# V1_9.net
KiCad netlist of a schematic drawn in Altium Designer
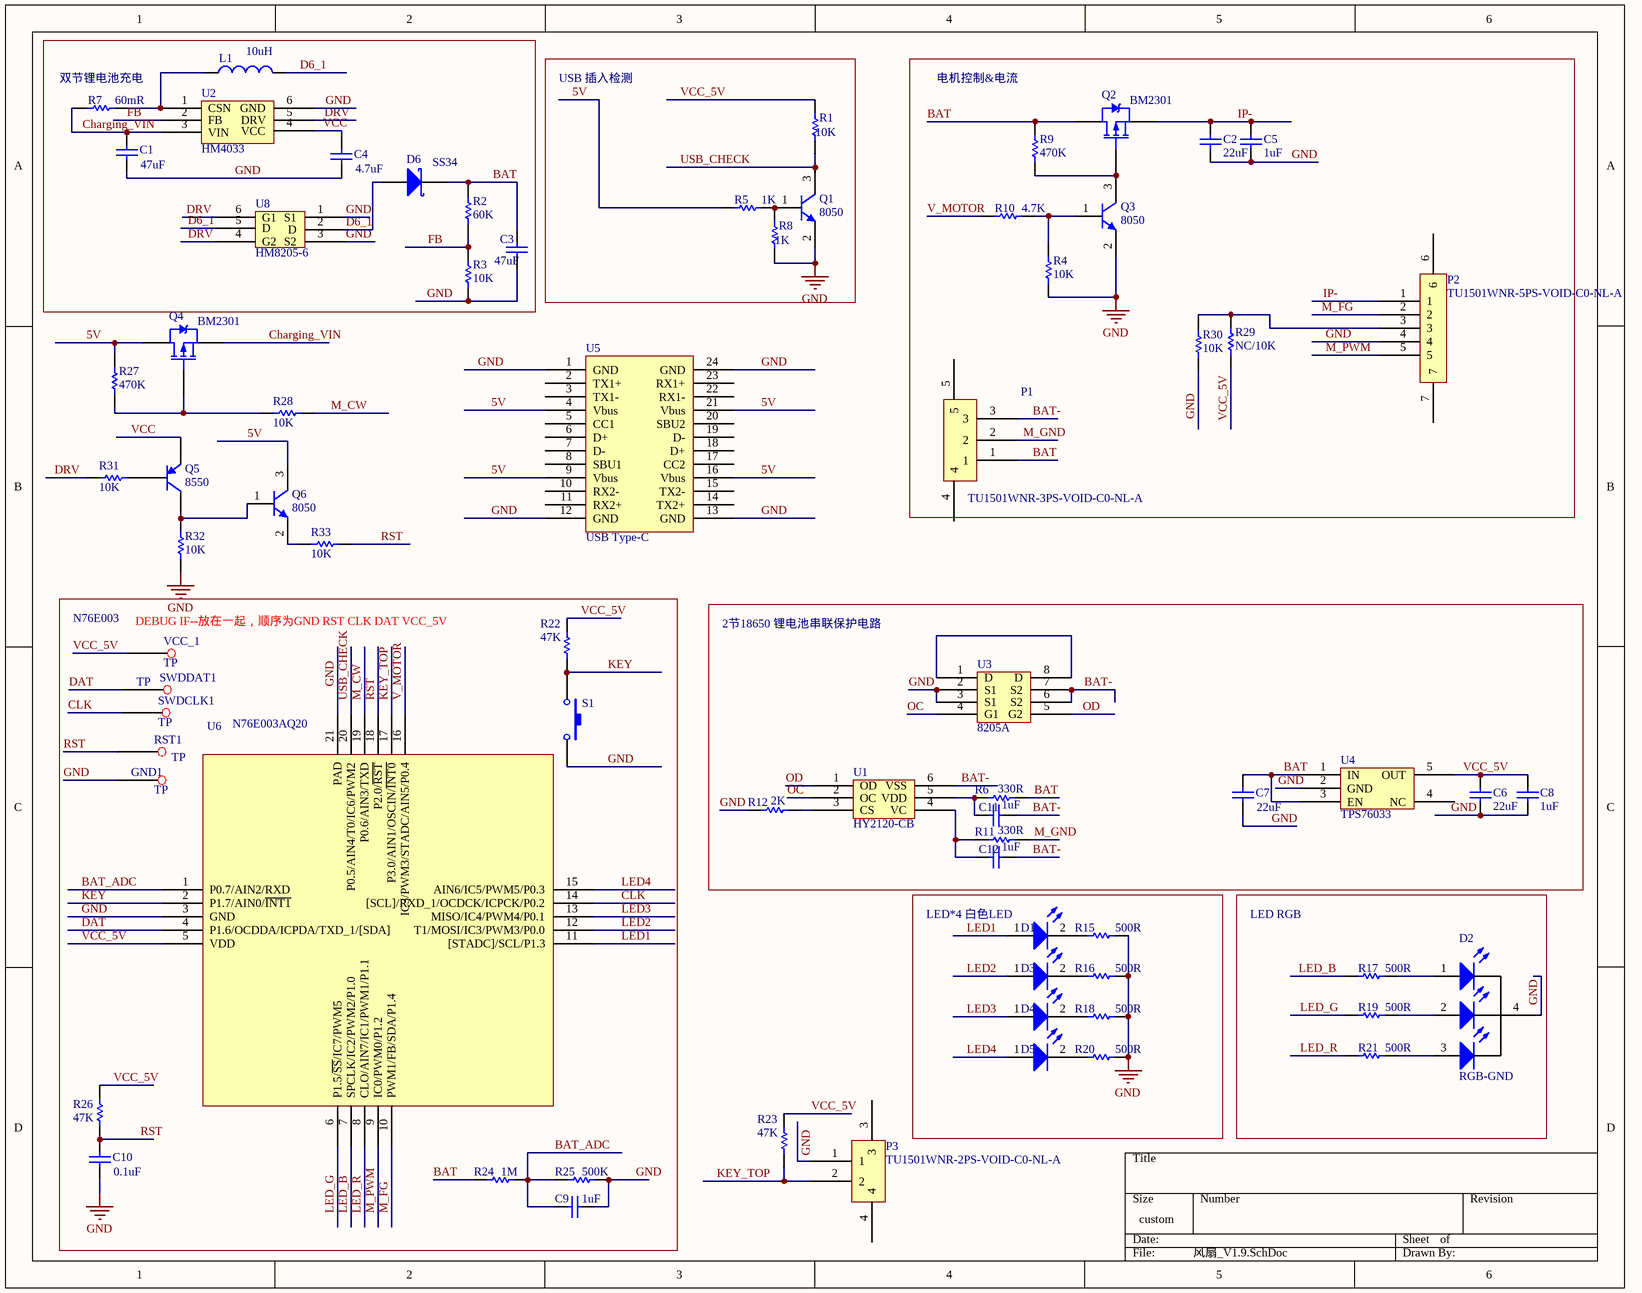
[diagram p0: 风扇_V1.9.SchDoc]

(export (version "E")
  (design (tool "Eeschema 10.0.6"))
  (components
    (comp (ref "C1")
      (value "47uF")
      (footprint "C-0603")
      (description "Capacitor")
      (fields (field (name "PUBLISHER") "Altium Limited"))
      (libsource (lib "Miscellaneous Devices") (part "Cap"))
    )
    (comp (ref "C2")
      (value "22uF")
      (footprint "C-0603")
      (description "Capacitor")
      (fields (field (name "PUBLISHER") "Altium Limited"))
      (libsource (lib "Miscellaneous Devices") (part "Cap"))
    )
    (comp (ref "C3")
      (value "47uF")
      (footprint "C-0603")
      (description "Capacitor")
      (fields (field (name "PUBLISHER") "Altium Limited"))
      (libsource (lib "Miscellaneous Devices") (part "Cap"))
    )
    (comp (ref "C4")
      (value "4.7uF")
      (footprint "C-0402")
      (description "Capacitor")
      (fields (field (name "PUBLISHER") "Altium Limited"))
      (libsource (lib "Miscellaneous Devices") (part "Cap"))
    )
    (comp (ref "C5")
      (value "1uF")
      (footprint "C-0402")
      (description "Capacitor")
      (fields (field (name "PUBLISHER") "Altium Limited"))
      (libsource (lib "Miscellaneous Devices") (part "Cap"))
    )
    (comp (ref "C6")
      (value "22uF")
      (footprint "C-0603")
      (description "Capacitor")
      (fields (field (name "PUBLISHER") "Altium Limited"))
      (libsource (lib "Miscellaneous Devices") (part "Cap"))
    )
    (comp (ref "C7")
      (value "22uF")
      (footprint "C-0603")
      (description "Capacitor")
      (fields (field (name "PUBLISHER") "Altium Limited"))
      (libsource (lib "Miscellaneous Devices") (part "Cap"))
    )
    (comp (ref "C8")
      (value "1uF")
      (footprint "C-0402")
      (description "Capacitor")
      (fields (field (name "PUBLISHER") "Altium Limited"))
      (libsource (lib "Miscellaneous Devices") (part "Cap"))
    )
    (comp (ref "C9")
      (value "1uF")
      (footprint "C-0402")
      (description "Capacitor")
      (fields (field (name "PUBLISHER") "Altium Limited"))
      (libsource (lib "Miscellaneous Devices") (part "Cap"))
    )
    (comp (ref "C10")
      (value "0.1uF")
      (footprint "C-0402")
      (description "Capacitor")
      (fields (field (name "PUBLISHER") "Altium Limited"))
      (libsource (lib "Miscellaneous Devices") (part "Cap"))
    )
    (comp (ref "C11")
      (value "1uF")
      (footprint "C-0402")
      (description "Capacitor")
      (fields (field (name "PUBLISHER") "Altium Limited"))
      (libsource (lib "Miscellaneous Devices") (part "Cap"))
    )
    (comp (ref "C12")
      (value "1uF")
      (footprint "C-0402")
      (description "Capacitor")
      (fields (field (name "PUBLISHER") "Altium Limited"))
      (libsource (lib "Miscellaneous Devices") (part "Cap"))
    )
    (comp (ref "D1")
      (value "LED0")
      (footprint "LED-0603")
      (description "Typical INFRARED GaAs LED")
      (fields (field (name "PUBLISHER") "Altium Limited"))
      (libsource (lib "Miscellaneous Devices") (part "LED0"))
    )
    (comp (ref "D2")
      (value "RGB-GND")
      (footprint "0603*2-LED")
      (libsource (lib "Others_IC_SCH_LIB") (part "RGB-GND"))
    )
    (comp (ref "D3")
      (value "LED0")
      (footprint "LED-0603")
      (description "Typical INFRARED GaAs LED")
      (fields (field (name "PUBLISHER") "Altium Limited"))
      (libsource (lib "Miscellaneous Devices") (part "LED0"))
    )
    (comp (ref "D4")
      (value "LED0")
      (footprint "LED-0603")
      (description "Typical INFRARED GaAs LED")
      (fields (field (name "PUBLISHER") "Altium Limited"))
      (libsource (lib "Miscellaneous Devices") (part "LED0"))
    )
    (comp (ref "D5")
      (value "LED0")
      (footprint "LED-0603")
      (description "Typical INFRARED GaAs LED")
      (fields (field (name "PUBLISHER") "Altium Limited"))
      (libsource (lib "Miscellaneous Devices") (part "LED0"))
    )
    (comp (ref "D6")
      (value "SS34")
      (footprint "HM4033 V1.0:DSMD")
      (description "Schottky Rectifier")
      (fields (field (name "PUBLISHER") "Altium Limited"))
      (libsource (lib "Miscellaneous Devices") (part "Diode 10TQ035"))
    )
    (comp (ref "GND1") (value "TP") (footprint "TP-1.5") (libsource (lib "Others_IC_SCH_LIB") (part "TP")))
    (comp (ref "L1")
      (value "10uH")
      (footprint "L-SMD")
      (description "Inductor")
      (fields (field (name "PUBLISHER") "Altium Limited"))
      (libsource (lib "Miscellaneous Devices") (part "Inductor"))
    )
    (comp (ref "P1")
      (value "TU1501WNR-3PS-VOID-C0-NL-A")
      (footprint "TU1501WNR-3PS-VOID-*-NL-A")
      (libsource (lib "Others_IC_SCH_LIB") (part "TU1501WNR-3PS-VOID-C0-NL-A"))
    )
    (comp (ref "P2")
      (value "TU1501WNR-5PS-VOID-C0-NL-A")
      (footprint "TU1501WNR-5PS-VOID-*-NL-A")
      (libsource (lib "Others_IC_SCH_LIB") (part "TU1501WNR-5PS-VOID-C0-NL-A"))
    )
    (comp (ref "P3")
      (value "TU1501WNR-2PS-VOID-C0-NL-A")
      (footprint "TU1501WNR-2PS-VOID-*-NL-A")
      (libsource (lib "Others_IC_SCH_LIB") (part "TU1501WNR-2PS-VOID-C0-NL-A"))
    )
    (comp (ref "Q1")
      (value "8050")
      (footprint "SOT-23")
      (description "NPN Bipolar Transistor")
      (fields (field (name "PUBLISHER") "Altium Limited"))
      (libsource (lib "Miscellaneous Devices") (part "NPN"))
    )
    (comp (ref "Q2")
      (value "BM2301")
      (footprint "SOT-23")
      (description "P-Channel Power MOSFET")
      (fields (field (name "PUBLISHER") "Altium Limited"))
      (libsource (lib "Miscellaneous Devices") (part "PMOS-2"))
    )
    (comp (ref "Q3")
      (value "8050")
      (footprint "SOT-23")
      (description "NPN Bipolar Transistor")
      (fields (field (name "PUBLISHER") "Altium Limited"))
      (libsource (lib "Miscellaneous Devices") (part "NPN"))
    )
    (comp (ref "Q4")
      (value "BM2301")
      (footprint "SOT-23")
      (description "P-Channel Power MOSFET")
      (fields (field (name "PUBLISHER") "Altium Limited"))
      (libsource (lib "Miscellaneous Devices") (part "PMOS-2"))
    )
    (comp (ref "Q5")
      (value "8550")
      (footprint "SOT95P240-3N")
      (description "PNP Bipolar Transistor")
      (fields (field (name "PUBLISHER") "Altium Limited"))
      (libsource (lib "Miscellaneous Devices") (part "PNP"))
    )
    (comp (ref "Q6")
      (value "8050")
      (footprint "SOT-23")
      (description "NPN Bipolar Transistor")
      (fields (field (name "PUBLISHER") "Altium Limited"))
      (libsource (lib "Miscellaneous Devices") (part "NPN"))
    )
    (comp (ref "R1")
      (value "10K")
      (footprint "R-0402")
      (description "Resistor")
      (fields (field (name "PUBLISHER") "Altium Limited"))
      (libsource (lib "Miscellaneous Devices") (part "Res1"))
    )
    (comp (ref "R2")
      (value "60K")
      (footprint "R-0402")
      (description "Resistor")
      (fields (field (name "PUBLISHER") "Altium Limited"))
      (libsource (lib "Miscellaneous Devices") (part "Res1"))
    )
    (comp (ref "R3")
      (value "10K")
      (footprint "R-0402")
      (description "Resistor")
      (fields (field (name "PUBLISHER") "Altium Limited"))
      (libsource (lib "Miscellaneous Devices") (part "Res1"))
    )
    (comp (ref "R4")
      (value "10K")
      (footprint "R-0402")
      (description "Resistor")
      (fields (field (name "PUBLISHER") "Altium Limited"))
      (libsource (lib "Miscellaneous Devices") (part "Res1"))
    )
    (comp (ref "R5")
      (value "1K")
      (footprint "R-0402")
      (description "Resistor")
      (fields (field (name "PUBLISHER") "Altium Limited"))
      (libsource (lib "Miscellaneous Devices") (part "Res1"))
    )
    (comp (ref "R6")
      (value "330R")
      (footprint "R-0402")
      (description "Resistor")
      (fields (field (name "PUBLISHER") "Altium Limited"))
      (libsource (lib "Miscellaneous Devices") (part "Res1"))
    )
    (comp (ref "R7")
      (value "60mR")
      (footprint "R-0402")
      (description "Resistor")
      (fields (field (name "PUBLISHER") "Altium Limited"))
      (libsource (lib "Miscellaneous Devices") (part "Res1"))
    )
    (comp (ref "R8")
      (value "1K")
      (footprint "R-0402")
      (description "Resistor")
      (fields (field (name "PUBLISHER") "Altium Limited"))
      (libsource (lib "Miscellaneous Devices") (part "Res1"))
    )
    (comp (ref "R9")
      (value "470K")
      (footprint "R-0402")
      (description "Resistor")
      (fields (field (name "PUBLISHER") "Altium Limited"))
      (libsource (lib "Miscellaneous Devices") (part "Res1"))
    )
    (comp (ref "R10")
      (value "4.7K")
      (footprint "R-0402")
      (description "Resistor")
      (fields (field (name "PUBLISHER") "Altium Limited"))
      (libsource (lib "Miscellaneous Devices") (part "Res1"))
    )
    (comp (ref "R11")
      (value "330R")
      (footprint "R-0402")
      (description "Resistor")
      (fields (field (name "PUBLISHER") "Altium Limited"))
      (libsource (lib "Miscellaneous Devices") (part "Res1"))
    )
    (comp (ref "R12")
      (value "2K")
      (footprint "R-0402")
      (description "Resistor")
      (fields (field (name "PUBLISHER") "Altium Limited"))
      (libsource (lib "Miscellaneous Devices") (part "Res1"))
    )
    (comp (ref "R15")
      (value "500R")
      (footprint "R-0402")
      (description "Resistor")
      (fields (field (name "PUBLISHER") "Altium Limited"))
      (libsource (lib "Miscellaneous Devices") (part "Res1"))
    )
    (comp (ref "R16")
      (value "500R")
      (footprint "R-0402")
      (description "Resistor")
      (fields (field (name "PUBLISHER") "Altium Limited"))
      (libsource (lib "Miscellaneous Devices") (part "Res1"))
    )
    (comp (ref "R17")
      (value "500R")
      (footprint "R-0402")
      (description "Resistor")
      (fields (field (name "PUBLISHER") "Altium Limited"))
      (libsource (lib "Miscellaneous Devices") (part "Res1"))
    )
    (comp (ref "R18")
      (value "500R")
      (footprint "R-0402")
      (description "Resistor")
      (fields (field (name "PUBLISHER") "Altium Limited"))
      (libsource (lib "Miscellaneous Devices") (part "Res1"))
    )
    (comp (ref "R19")
      (value "500R")
      (footprint "R-0402")
      (description "Resistor")
      (fields (field (name "PUBLISHER") "Altium Limited"))
      (libsource (lib "Miscellaneous Devices") (part "Res1"))
    )
    (comp (ref "R20")
      (value "500R")
      (footprint "R-0402")
      (description "Resistor")
      (fields (field (name "PUBLISHER") "Altium Limited"))
      (libsource (lib "Miscellaneous Devices") (part "Res1"))
    )
    (comp (ref "R21")
      (value "500R")
      (footprint "R-0402")
      (description "Resistor")
      (fields (field (name "PUBLISHER") "Altium Limited"))
      (libsource (lib "Miscellaneous Devices") (part "Res1"))
    )
    (comp (ref "R22")
      (value "47K")
      (footprint "R-0402")
      (description "Resistor")
      (fields (field (name "PUBLISHER") "Altium Limited"))
      (libsource (lib "Miscellaneous Devices") (part "Res1"))
    )
    (comp (ref "R23")
      (value "47K")
      (footprint "R-0402")
      (description "Resistor")
      (fields (field (name "PUBLISHER") "Altium Limited"))
      (libsource (lib "Miscellaneous Devices") (part "Res1"))
    )
    (comp (ref "R24")
      (value "1M")
      (footprint "R-0402")
      (description "Resistor")
      (fields (field (name "PUBLISHER") "Altium Limited"))
      (libsource (lib "Miscellaneous Devices") (part "Res1"))
    )
    (comp (ref "R25")
      (value "500K")
      (footprint "R-0402")
      (description "Resistor")
      (fields (field (name "PUBLISHER") "Altium Limited"))
      (libsource (lib "Miscellaneous Devices") (part "Res1"))
    )
    (comp (ref "R26")
      (value "47K")
      (footprint "R-0402")
      (description "Resistor")
      (fields (field (name "PUBLISHER") "Altium Limited"))
      (libsource (lib "Miscellaneous Devices") (part "Res1"))
    )
    (comp (ref "R27")
      (value "470K")
      (footprint "R-0402")
      (description "Resistor")
      (fields (field (name "PUBLISHER") "Altium Limited"))
      (libsource (lib "Miscellaneous Devices") (part "Res1"))
    )
    (comp (ref "R28")
      (value "10K")
      (footprint "R-0402")
      (description "Resistor")
      (fields (field (name "PUBLISHER") "Altium Limited"))
      (libsource (lib "Miscellaneous Devices") (part "Res1"))
    )
    (comp (ref "R29")
      (value "NC/10K")
      (footprint "R-0402")
      (description "Resistor")
      (fields (field (name "PUBLISHER") "Altium Limited"))
      (libsource (lib "Miscellaneous Devices") (part "Res1"))
    )
    (comp (ref "R30")
      (value "10K")
      (footprint "R-0402")
      (description "Resistor")
      (fields (field (name "PUBLISHER") "Altium Limited"))
      (libsource (lib "Miscellaneous Devices") (part "Res1"))
    )
    (comp (ref "R31")
      (value "10K")
      (footprint "R-0402")
      (description "Resistor")
      (fields (field (name "PUBLISHER") "Altium Limited"))
      (libsource (lib "Miscellaneous Devices") (part "Res1"))
    )
    (comp (ref "R32")
      (value "10K")
      (footprint "R-0402")
      (description "Resistor")
      (fields (field (name "PUBLISHER") "Altium Limited"))
      (libsource (lib "Miscellaneous Devices") (part "Res1"))
    )
    (comp (ref "R33")
      (value "10K")
      (footprint "R-0402")
      (description "Resistor")
      (fields (field (name "PUBLISHER") "Altium Limited"))
      (libsource (lib "Miscellaneous Devices") (part "Res1"))
    )
    (comp (ref "RST1") (value "TP") (footprint "TP-1.5") (libsource (lib "Others_IC_SCH_LIB") (part "TP")))
    (comp (ref "S1")
      (value "SW-PB")
      (footprint "SWITCH-4P-SMT")
      (description "Switch")
      (fields (field (name "PUBLISHER") "Altium Limited"))
      (libsource (lib "Miscellaneous Devices") (part "SW-PB"))
    )
    (comp (ref "SWDCLK1") (value "TP") (footprint "TP-1.5") (libsource (lib "Others_IC_SCH_LIB") (part "TP")))
    (comp (ref "SWDDAT1") (value "TP") (footprint "TP-1.5") (libsource (lib "Others_IC_SCH_LIB") (part "TP")))
    (comp (ref "U1")
      (value "HY2120-CB")
      (footprint "SOT-23-6L")
      (libsource (lib "Others_IC_SCH_LIB") (part "HY2120"))
    )
    (comp (ref "U2")
      (value "HM4033")
      (footprint "SOT-23-6L")
      (libsource (lib "Others_IC_SCH_LIB") (part "HM4033"))
    )
    (comp (ref "U3")
      (value "8205A")
      (footprint "TSSOP8")
      (libsource (lib "Others_IC_SCH_LIB") (part "8205A"))
    )
    (comp (ref "U4")
      (value "TPS76033")
      (footprint "SOT-23-5")
      (libsource (lib "Others_IC_SCH_LIB") (part "TPS76033"))
    )
    (comp (ref "U5")
      (value "USB Type-C")
      (footprint "USB-type C")
      (libsource (lib "Others_IC_SCH_LIB") (part "USB Type-C"))
    )
    (comp (ref "U6")
      (value "N76E003AQ20")
      (footprint "QFN-20 0.4mm")
      (libsource (lib "Others_IC_SCH_LIB") (part "N76E003AQ20"))
    )
    (comp (ref "U8")
      (value "HM8205-6")
      (footprint "SOT-23-6L")
      (libsource (lib "Others_IC_SCH_LIB") (part "HM8205-6"))
    )
    (comp (ref "VCC_1") (value "TP") (footprint "TP-1.5") (libsource (lib "Others_IC_SCH_LIB") (part "TP")))
  )
  (nets
    (net (code "1") (name "/5V") (class "Default")
      (node (ref "Q4") (pin "2") (pinfunction "D_2") (pintype "passive"))
      (node (ref "Q6") (pin "3") (pinfunction "C_3") (pintype "passive"))
      (node (ref "R27") (pin "2") (pinfunction "2_2") (pintype "passive"))
      (node (ref "R5") (pin "1") (pinfunction "1_1") (pintype "passive"))
      (node (ref "U5") (pin "16") (pinfunction "Vbus_16") (pintype "passive"))
      (node (ref "U5") (pin "21") (pinfunction "Vbus_21") (pintype "passive"))
      (node (ref "U5") (pin "4") (pinfunction "Vbus_4") (pintype "passive"))
      (node (ref "U5") (pin "9") (pinfunction "Vbus_9") (pintype "passive"))
    )
    (net (code "2") (name "/BAT") (class "Default")
      (node (ref "C3") (pin "2") (pinfunction "2_2") (pintype "passive"))
      (node (ref "C7") (pin "2") (pinfunction "2_2") (pintype "passive"))
      (node (ref "D6") (pin "1") (pinfunction "K_1") (pintype "passive"))
      (node (ref "P1") (pin "1") (pinfunction "1_1") (pintype "passive"))
      (node (ref "Q2") (pin "2") (pinfunction "D_2") (pintype "passive"))
      (node (ref "R2") (pin "1") (pinfunction "1_1") (pintype "passive"))
      (node (ref "R24") (pin "1") (pinfunction "1_1") (pintype "passive"))
      (node (ref "R6") (pin "2") (pinfunction "2_2") (pintype "passive"))
      (node (ref "R9") (pin "2") (pinfunction "2_2") (pintype "passive"))
      (node (ref "U4") (pin "1") (pinfunction "IN_1") (pintype "passive"))
      (node (ref "U4") (pin "3") (pinfunction "EN_3") (pintype "passive"))
    )
    (net (code "3") (name "/BAT-") (class "Default")
      (node (ref "C11") (pin "1") (pinfunction "1_1") (pintype "passive"))
      (node (ref "C12") (pin "1") (pinfunction "1_1") (pintype "passive"))
      (node (ref "P1") (pin "3") (pinfunction "3_3") (pintype "passive"))
      (node (ref "U1") (pin "6") (pinfunction "VSS_6") (pintype "passive"))
      (node (ref "U3") (pin "6") (pinfunction "S2_6") (pintype "passive"))
      (node (ref "U3") (pin "7") (pinfunction "S2_7") (pintype "passive"))
    )
    (net (code "4") (name "/BAT_ADC") (class "Default")
      (node (ref "C9") (pin "2") (pinfunction "2_2") (pintype "passive"))
      (node (ref "R24") (pin "2") (pinfunction "2_2") (pintype "passive"))
      (node (ref "R25") (pin "1") (pinfunction "1_1") (pintype "passive"))
      (node (ref "U6") (pin "1") (pinfunction "P0.7/AIN2/RXD_1") (pintype "passive"))
    )
    (net (code "5") (name "/CLK") (class "Default")
      (node (ref "SWDCLK1") (pin "1") (pinfunction "1_1") (pintype "passive"))
      (node (ref "U6") (pin "14") (pinfunction "[SCL]/RXD_1/OCDCK/ICPCK/P0.2_14") (pintype "passive"))
    )
    (net (code "6") (name "/Charging_VIN") (class "Default")
      (node (ref "C1") (pin "1") (pinfunction "1_1") (pintype "passive"))
      (node (ref "Q4") (pin "3") (pinfunction "S_3") (pintype "passive"))
      (node (ref "R7") (pin "2") (pinfunction "2_2") (pintype "passive"))
      (node (ref "U2") (pin "3") (pinfunction "VIN_3") (pintype "passive"))
    )
    (net (code "7") (name "/D6_1") (class "Default")
      (node (ref "D6") (pin "3") (pinfunction "A_3") (pintype "passive"))
      (node (ref "L1") (pin "2") (pinfunction "2_2") (pintype "passive"))
      (node (ref "U8") (pin "2") (pinfunction "D_2") (pintype "passive"))
      (node (ref "U8") (pin "5") (pinfunction "D_5") (pintype "passive"))
    )
    (net (code "8") (name "/DAT") (class "Default")
      (node (ref "SWDDAT1") (pin "1") (pinfunction "1_1") (pintype "passive"))
      (node (ref "U6") (pin "4") (pinfunction "P1.6/OCDDA/ICPDA/TXD_1/[SDA]_4") (pintype "passive"))
    )
    (net (code "9") (name "/DRV") (class "Default")
      (node (ref "R31") (pin "1") (pinfunction "1_1") (pintype "passive"))
      (node (ref "U2") (pin "5") (pinfunction "DRV_5") (pintype "passive"))
      (node (ref "U8") (pin "4") (pinfunction "G2_4") (pintype "passive"))
      (node (ref "U8") (pin "6") (pinfunction "G1_6") (pintype "passive"))
    )
    (net (code "10") (name "/FB") (class "Default")
      (node (ref "R2") (pin "2") (pinfunction "2_2") (pintype "passive"))
      (node (ref "R3") (pin "1") (pinfunction "1_1") (pintype "passive"))
      (node (ref "U2") (pin "2") (pinfunction "FB_2") (pintype "passive"))
    )
    (net (code "11") (name "/IP-") (class "Default")
      (node (ref "C2") (pin "2") (pinfunction "2_2") (pintype "passive"))
      (node (ref "C5") (pin "2") (pinfunction "2_2") (pintype "passive"))
      (node (ref "P2") (pin "1") (pinfunction "1_1") (pintype "passive"))
      (node (ref "Q2") (pin "3") (pinfunction "S_3") (pintype "passive"))
    )
    (net (code "12") (name "/KEY") (class "Default")
      (node (ref "R22") (pin "1") (pinfunction "1_1") (pintype "passive"))
      (node (ref "S1") (pin "1") (pinfunction "1_1") (pintype "passive"))
      (node (ref "U6") (pin "2") (pinfunction "P1.7/AIN0/~{INT1}_2") (pintype "passive"))
    )
    (net (code "13") (name "/KEY_TOP") (class "Default")
      (node (ref "P3") (pin "2") (pinfunction "2_2") (pintype "passive"))
      (node (ref "R23") (pin "1") (pinfunction "1_1") (pintype "passive"))
      (node (ref "U6") (pin "17") (pinfunction "P3.0/AIN1/OSCIN/~{INT0}_17") (pintype "passive"))
    )
    (net (code "14") (name "/LED1") (class "Default")
      (node (ref "D1") (pin "1") (pinfunction "A_1") (pintype "passive"))
      (node (ref "U6") (pin "11") (pinfunction "[STADC]/SCL/P1.3_11") (pintype "passive"))
    )
    (net (code "15") (name "/LED2") (class "Default")
      (node (ref "D3") (pin "1") (pinfunction "A_1") (pintype "passive"))
      (node (ref "U6") (pin "12") (pinfunction "T1/MOSI/IC3/PWM3/P0.0_12") (pintype "passive"))
    )
    (net (code "16") (name "/LED3") (class "Default")
      (node (ref "D4") (pin "1") (pinfunction "A_1") (pintype "passive"))
      (node (ref "U6") (pin "13") (pinfunction "MISO/IC4/PWM4/P0.1_13") (pintype "passive"))
    )
    (net (code "17") (name "/LED4") (class "Default")
      (node (ref "D5") (pin "1") (pinfunction "A_1") (pintype "passive"))
      (node (ref "U6") (pin "15") (pinfunction "AIN6/IC5/PWM5/P0.3_15") (pintype "passive"))
    )
    (net (code "18") (name "/LED_B") (class "Default")
      (node (ref "R17") (pin "1") (pinfunction "1_1") (pintype "passive"))
      (node (ref "U6") (pin "7") (pinfunction "SPCLK/IC2/PWM2/P1.0_7") (pintype "passive"))
    )
    (net (code "19") (name "/LED_G") (class "Default")
      (node (ref "R19") (pin "1") (pinfunction "1_1") (pintype "passive"))
      (node (ref "U6") (pin "6") (pinfunction "P1.5/~{SS}/IC7/PWM5_6") (pintype "passive"))
    )
    (net (code "20") (name "/LED_R") (class "Default")
      (node (ref "R21") (pin "1") (pinfunction "1_1") (pintype "passive"))
      (node (ref "U6") (pin "8") (pinfunction "CLO/AIN7/IC1/PWM1/P1.1_8") (pintype "passive"))
    )
    (net (code "21") (name "/M_CW") (class "Default")
      (node (ref "R28") (pin "1") (pinfunction "1_1") (pintype "passive"))
      (node (ref "U6") (pin "19") (pinfunction "P0.6/AIN3/TXD_19") (pintype "passive"))
    )
    (net (code "22") (name "/M_FG") (class "Default")
      (node (ref "P2") (pin "2") (pinfunction "2_2") (pintype "passive"))
      (node (ref "U6") (pin "10") (pinfunction "PWM1/FB/SDA/P1.4_10") (pintype "passive"))
    )
    (net (code "23") (name "/M_GND") (class "Default")
      (node (ref "P1") (pin "2") (pinfunction "2_2") (pintype "passive"))
      (node (ref "R11") (pin "2") (pinfunction "2_2") (pintype "passive"))
    )
    (net (code "24") (name "/M_PWM") (class "Default")
      (node (ref "P2") (pin "5") (pinfunction "5_5") (pintype "passive"))
      (node (ref "U6") (pin "9") (pinfunction "IC0/PWM0/P1.2_9") (pintype "passive"))
    )
    (net (code "25") (name "/OC") (class "Default")
      (node (ref "U1") (pin "2") (pinfunction "OC_2") (pintype "passive"))
      (node (ref "U3") (pin "4") (pinfunction "G1_4") (pintype "passive"))
    )
    (net (code "26") (name "/OD") (class "Default")
      (node (ref "U1") (pin "1") (pinfunction "OD_1") (pintype "passive"))
      (node (ref "U3") (pin "5") (pinfunction "G2_5") (pintype "passive"))
    )
    (net (code "27") (name "/RST") (class "Default")
      (node (ref "C10") (pin "2") (pinfunction "2_2") (pintype "passive"))
      (node (ref "R26") (pin "1") (pinfunction "1_1") (pintype "passive"))
      (node (ref "R33") (pin "1") (pinfunction "1_1") (pintype "passive"))
      (node (ref "RST1") (pin "1") (pinfunction "1_1") (pintype "passive"))
      (node (ref "U6") (pin "18") (pinfunction "P2.0/~{RST}_18") (pintype "passive"))
    )
    (net (code "28") (name "/USB_CHECK") (class "Default")
      (node (ref "Q1") (pin "3") (pinfunction "C_3") (pintype "passive"))
      (node (ref "R1") (pin "1") (pinfunction "1_1") (pintype "passive"))
      (node (ref "U6") (pin "20") (pinfunction "P0.5/AIN4/T0/IC6/PWM2_20") (pintype "passive"))
    )
    (net (code "29") (name "/VCC") (class "Default")
      (node (ref "C4") (pin "1") (pinfunction "1_1") (pintype "passive"))
      (node (ref "Q5") (pin "3") (pinfunction "E_3") (pintype "passive"))
      (node (ref "U2") (pin "4") (pinfunction "VCC_4") (pintype "passive"))
    )
    (net (code "30") (name "/VCC_5V") (class "Default")
      (node (ref "C6") (pin "2") (pinfunction "2_2") (pintype "passive"))
      (node (ref "C8") (pin "2") (pinfunction "2_2") (pintype "passive"))
      (node (ref "R1") (pin "2") (pinfunction "2_2") (pintype "passive"))
      (node (ref "R22") (pin "2") (pinfunction "2_2") (pintype "passive"))
      (node (ref "R23") (pin "2") (pinfunction "2_2") (pintype "passive"))
      (node (ref "R26") (pin "2") (pinfunction "2_2") (pintype "passive"))
      (node (ref "R29") (pin "2") (pinfunction "2_2") (pintype "passive"))
      (node (ref "U4") (pin "5") (pinfunction "OUT_5") (pintype "passive"))
      (node (ref "U6") (pin "5") (pinfunction "VDD_5") (pintype "passive"))
      (node (ref "VCC_1") (pin "1") (pinfunction "1_1") (pintype "passive"))
    )
    (net (code "31") (name "/V_MOTOR") (class "Default")
      (node (ref "R10") (pin "1") (pinfunction "1_1") (pintype "passive"))
      (node (ref "U6") (pin "16") (pinfunction "IC3/PWM3/STADC/AIN5/P0.4_16") (pintype "passive"))
    )
    (net (code "32") (name "GND") (class "Default")
      (node (ref "C1") (pin "2") (pinfunction "2_2") (pintype "passive"))
      (node (ref "C10") (pin "1") (pinfunction "1_1") (pintype "passive"))
      (node (ref "C2") (pin "1") (pinfunction "1_1") (pintype "passive"))
      (node (ref "C3") (pin "1") (pinfunction "1_1") (pintype "passive"))
      (node (ref "C4") (pin "2") (pinfunction "2_2") (pintype "passive"))
      (node (ref "C5") (pin "1") (pinfunction "1_1") (pintype "passive"))
      (node (ref "C6") (pin "1") (pinfunction "1_1") (pintype "passive"))
      (node (ref "C7") (pin "1") (pinfunction "1_1") (pintype "passive"))
      (node (ref "C8") (pin "1") (pinfunction "1_1") (pintype "passive"))
      (node (ref "C9") (pin "1") (pinfunction "1_1") (pintype "passive"))
      (node (ref "D2") (pin "4") (pinfunction "4_4") (pintype "passive"))
      (node (ref "GND1") (pin "1") (pinfunction "1_1") (pintype "passive"))
      (node (ref "P2") (pin "4") (pinfunction "4_4") (pintype "passive"))
      (node (ref "P3") (pin "1") (pinfunction "1_1") (pintype "passive"))
      (node (ref "Q1") (pin "2") (pinfunction "E_2") (pintype "passive"))
      (node (ref "Q3") (pin "2") (pinfunction "E_2") (pintype "passive"))
      (node (ref "R12") (pin "1") (pinfunction "1_1") (pintype "passive"))
      (node (ref "R15") (pin "2") (pinfunction "2_2") (pintype "passive"))
      (node (ref "R16") (pin "2") (pinfunction "2_2") (pintype "passive"))
      (node (ref "R18") (pin "2") (pinfunction "2_2") (pintype "passive"))
      (node (ref "R20") (pin "2") (pinfunction "2_2") (pintype "passive"))
      (node (ref "R25") (pin "2") (pinfunction "2_2") (pintype "passive"))
      (node (ref "R3") (pin "2") (pinfunction "2_2") (pintype "passive"))
      (node (ref "R30") (pin "2") (pinfunction "2_2") (pintype "passive"))
      (node (ref "R32") (pin "1") (pinfunction "1_1") (pintype "passive"))
      (node (ref "R4") (pin "1") (pinfunction "1_1") (pintype "passive"))
      (node (ref "R8") (pin "2") (pinfunction "2_2") (pintype "passive"))
      (node (ref "S1") (pin "2") (pinfunction "2_2") (pintype "passive"))
      (node (ref "U2") (pin "6") (pinfunction "GND_6") (pintype "passive"))
      (node (ref "U3") (pin "2") (pinfunction "S1_2") (pintype "passive"))
      (node (ref "U3") (pin "3") (pinfunction "S1_3") (pintype "passive"))
      (node (ref "U4") (pin "2") (pinfunction "GND_2") (pintype "passive"))
      (node (ref "U5") (pin "1") (pinfunction "GND_1") (pintype "passive"))
      (node (ref "U5") (pin "12") (pinfunction "GND_12") (pintype "passive"))
      (node (ref "U5") (pin "13") (pinfunction "GND_13") (pintype "passive"))
      (node (ref "U5") (pin "24") (pinfunction "GND_24") (pintype "passive"))
      (node (ref "U6") (pin "21") (pinfunction "PAD_21") (pintype "passive"))
      (node (ref "U6") (pin "3") (pinfunction "GND_3") (pintype "passive"))
      (node (ref "U8") (pin "1") (pinfunction "S1_1") (pintype "passive"))
      (node (ref "U8") (pin "3") (pinfunction "S2_3") (pintype "passive"))
    )
    (net (code "33") (name "Net-(D1-K)") (class "Default")
      (node (ref "D1") (pin "2") (pinfunction "K_2") (pintype "passive"))
      (node (ref "R15") (pin "1") (pinfunction "1_1") (pintype "passive"))
    )
    (net (code "34") (name "Net-(D2-Pad1)") (class "Default")
      (node (ref "D2") (pin "1") (pinfunction "1_1") (pintype "passive"))
      (node (ref "R17") (pin "2") (pinfunction "2_2") (pintype "passive"))
    )
    (net (code "35") (name "Net-(D2-Pad2)") (class "Default")
      (node (ref "D2") (pin "2") (pinfunction "2_2") (pintype "passive"))
      (node (ref "R19") (pin "2") (pinfunction "2_2") (pintype "passive"))
    )
    (net (code "36") (name "Net-(D2-Pad3)") (class "Default")
      (node (ref "D2") (pin "3") (pinfunction "3_3") (pintype "passive"))
      (node (ref "R21") (pin "2") (pinfunction "2_2") (pintype "passive"))
    )
    (net (code "37") (name "Net-(D3-K)") (class "Default")
      (node (ref "D3") (pin "2") (pinfunction "K_2") (pintype "passive"))
      (node (ref "R16") (pin "1") (pinfunction "1_1") (pintype "passive"))
    )
    (net (code "38") (name "Net-(D4-K)") (class "Default")
      (node (ref "D4") (pin "2") (pinfunction "K_2") (pintype "passive"))
      (node (ref "R18") (pin "1") (pinfunction "1_1") (pintype "passive"))
    )
    (net (code "39") (name "Net-(D5-K)") (class "Default")
      (node (ref "D5") (pin "2") (pinfunction "K_2") (pintype "passive"))
      (node (ref "R20") (pin "1") (pinfunction "1_1") (pintype "passive"))
    )
    (net (code "40") (name "Net-(P2-Pad3)") (class "Default")
      (node (ref "P2") (pin "3") (pinfunction "3_3") (pintype "passive"))
      (node (ref "R29") (pin "1") (pinfunction "1_1") (pintype "passive"))
      (node (ref "R30") (pin "1") (pinfunction "1_1") (pintype "passive"))
    )
    (net (code "41") (name "Net-(Q1-B)") (class "Default")
      (node (ref "Q1") (pin "1") (pinfunction "B_1") (pintype "passive"))
      (node (ref "R5") (pin "2") (pinfunction "2_2") (pintype "passive"))
      (node (ref "R8") (pin "1") (pinfunction "1_1") (pintype "passive"))
    )
    (net (code "42") (name "Net-(Q2-G)") (class "Default")
      (node (ref "Q2") (pin "1") (pinfunction "G_1") (pintype "passive"))
      (node (ref "Q3") (pin "3") (pinfunction "C_3") (pintype "passive"))
      (node (ref "R9") (pin "1") (pinfunction "1_1") (pintype "passive"))
    )
    (net (code "43") (name "Net-(Q3-B)") (class "Default")
      (node (ref "Q3") (pin "1") (pinfunction "B_1") (pintype "passive"))
      (node (ref "R10") (pin "2") (pinfunction "2_2") (pintype "passive"))
      (node (ref "R4") (pin "2") (pinfunction "2_2") (pintype "passive"))
    )
    (net (code "44") (name "Net-(Q4-G)") (class "Default")
      (node (ref "Q4") (pin "1") (pinfunction "G_1") (pintype "passive"))
      (node (ref "R27") (pin "1") (pinfunction "1_1") (pintype "passive"))
      (node (ref "R28") (pin "2") (pinfunction "2_2") (pintype "passive"))
    )
    (net (code "45") (name "Net-(Q5-B)") (class "Default")
      (node (ref "Q5") (pin "2") (pinfunction "B_2") (pintype "passive"))
      (node (ref "R31") (pin "2") (pinfunction "2_2") (pintype "passive"))
    )
    (net (code "46") (name "Net-(Q5-C)") (class "Default")
      (node (ref "Q5") (pin "1") (pinfunction "C_1") (pintype "passive"))
      (node (ref "Q6") (pin "1") (pinfunction "B_1") (pintype "passive"))
      (node (ref "R32") (pin "2") (pinfunction "2_2") (pintype "passive"))
    )
    (net (code "47") (name "Net-(Q6-E)") (class "Default")
      (node (ref "Q6") (pin "2") (pinfunction "E_2") (pintype "passive"))
      (node (ref "R33") (pin "2") (pinfunction "2_2") (pintype "passive"))
    )
    (net (code "48") (name "Net-(U1-CS)") (class "Default")
      (node (ref "R12") (pin "2") (pinfunction "2_2") (pintype "passive"))
      (node (ref "U1") (pin "3") (pinfunction "CS_3") (pintype "passive"))
    )
    (net (code "49") (name "Net-(U1-VC)") (class "Default")
      (node (ref "C12") (pin "2") (pinfunction "2_2") (pintype "passive"))
      (node (ref "R11") (pin "1") (pinfunction "1_1") (pintype "passive"))
      (node (ref "U1") (pin "4") (pinfunction "VC_4") (pintype "passive"))
    )
    (net (code "50") (name "Net-(U1-VDD)") (class "Default")
      (node (ref "C11") (pin "2") (pinfunction "2_2") (pintype "passive"))
      (node (ref "R6") (pin "1") (pinfunction "1_1") (pintype "passive"))
      (node (ref "U1") (pin "5") (pinfunction "VDD_5") (pintype "passive"))
    )
    (net (code "51") (name "Net-(U2-CSN)") (class "Default")
      (node (ref "L1") (pin "1") (pinfunction "1_1") (pintype "passive"))
      (node (ref "R7") (pin "1") (pinfunction "1_1") (pintype "passive"))
      (node (ref "U2") (pin "1") (pinfunction "CSN_1") (pintype "passive"))
    )
    (net (code "52") (name "Net-(U3-D-Pad1)") (class "Default")
      (node (ref "U3") (pin "1") (pinfunction "D_1") (pintype "passive"))
      (node (ref "U3") (pin "8") (pinfunction "D_8") (pintype "passive"))
    )
    (net (code "53") (name "unconnected-(P1-Pad4)") (class "Default")
      (node (ref "P1") (pin "4") (pinfunction "4_4") (pintype "passive"))
    )
    (net (code "54") (name "unconnected-(P1-Pad5)") (class "Default")
      (node (ref "P1") (pin "5") (pinfunction "5_5") (pintype "passive"))
    )
    (net (code "55") (name "unconnected-(P2-Pad6)") (class "Default")
      (node (ref "P2") (pin "6") (pinfunction "6_6") (pintype "passive"))
    )
    (net (code "56") (name "unconnected-(P2-Pad7)") (class "Default")
      (node (ref "P2") (pin "7") (pinfunction "7_7") (pintype "passive"))
    )
    (net (code "57") (name "unconnected-(P3-Pad3)") (class "Default")
      (node (ref "P3") (pin "3") (pinfunction "3_3") (pintype "passive"))
    )
    (net (code "58") (name "unconnected-(P3-Pad4)") (class "Default")
      (node (ref "P3") (pin "4") (pinfunction "4_4") (pintype "passive"))
    )
    (net (code "59") (name "unconnected-(U4-NC-Pad4)") (class "Default")
      (node (ref "U4") (pin "4") (pinfunction "NC_4") (pintype "passive"))
    )
    (net (code "60") (name "unconnected-(U5-CC1-Pad5)") (class "Default")
      (node (ref "U5") (pin "5") (pinfunction "CC1_5") (pintype "passive"))
    )
    (net (code "61") (name "unconnected-(U5-CC2-Pad17)") (class "Default")
      (node (ref "U5") (pin "17") (pinfunction "CC2_17") (pintype "passive"))
    )
    (net (code "62") (name "unconnected-(U5-D+-Pad6)") (class "Default")
      (node (ref "U5") (pin "6") (pinfunction "D+_6") (pintype "passive"))
    )
    (net (code "63") (name "unconnected-(U5-D+-Pad18)") (class "Default")
      (node (ref "U5") (pin "18") (pinfunction "D+_18") (pintype "passive"))
    )
    (net (code "64") (name "unconnected-(U5-D--Pad7)") (class "Default")
      (node (ref "U5") (pin "7") (pinfunction "D-_7") (pintype "passive"))
    )
    (net (code "65") (name "unconnected-(U5-D--Pad19)") (class "Default")
      (node (ref "U5") (pin "19") (pinfunction "D-_19") (pintype "passive"))
    )
    (net (code "66") (name "unconnected-(U5-RX1+-Pad23)") (class "Default")
      (node (ref "U5") (pin "23") (pinfunction "RX1+_23") (pintype "passive"))
    )
    (net (code "67") (name "unconnected-(U5-RX1--Pad22)") (class "Default")
      (node (ref "U5") (pin "22") (pinfunction "RX1-_22") (pintype "passive"))
    )
    (net (code "68") (name "unconnected-(U5-RX2+-Pad11)") (class "Default")
      (node (ref "U5") (pin "11") (pinfunction "RX2+_11") (pintype "passive"))
    )
    (net (code "69") (name "unconnected-(U5-RX2--Pad10)") (class "Default")
      (node (ref "U5") (pin "10") (pinfunction "RX2-_10") (pintype "passive"))
    )
    (net (code "70") (name "unconnected-(U5-SBU1-Pad8)") (class "Default")
      (node (ref "U5") (pin "8") (pinfunction "SBU1_8") (pintype "passive"))
    )
    (net (code "71") (name "unconnected-(U5-SBU2-Pad20)") (class "Default")
      (node (ref "U5") (pin "20") (pinfunction "SBU2_20") (pintype "passive"))
    )
    (net (code "72") (name "unconnected-(U5-TX1+-Pad2)") (class "Default")
      (node (ref "U5") (pin "2") (pinfunction "TX1+_2") (pintype "passive"))
    )
    (net (code "73") (name "unconnected-(U5-TX1--Pad3)") (class "Default")
      (node (ref "U5") (pin "3") (pinfunction "TX1-_3") (pintype "passive"))
    )
    (net (code "74") (name "unconnected-(U5-TX2+-Pad14)") (class "Default")
      (node (ref "U5") (pin "14") (pinfunction "TX2+_14") (pintype "passive"))
    )
    (net (code "75") (name "unconnected-(U5-TX2--Pad15)") (class "Default")
      (node (ref "U5") (pin "15") (pinfunction "TX2-_15") (pintype "passive"))
    )
  )
)
